# NFC_NXP.net
KiCad netlist of a schematic drawn in Altium Designer
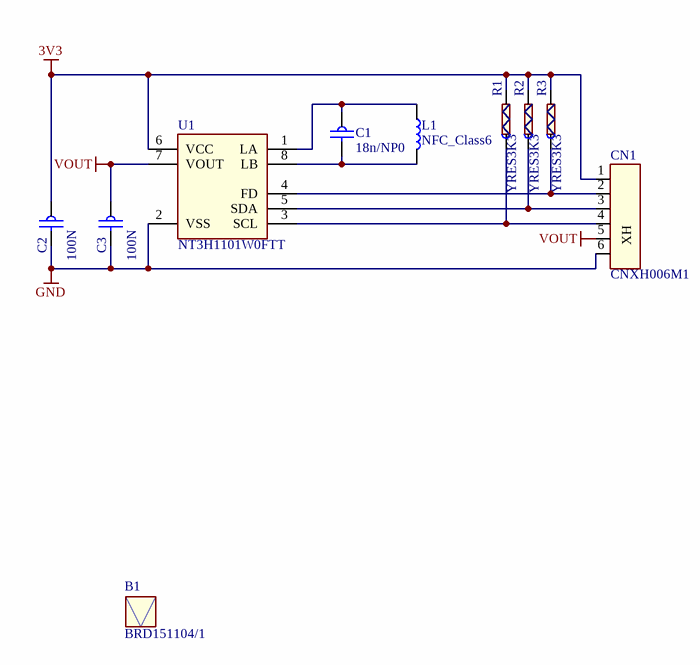
[diagram p0: NFC_NXP.SchDoc]

(export (version "E")
  (design (tool "Eeschema 10.0.6"))
  (components
    (comp (ref "B1")
      (value "~")
      (footprint "MC_BoardNr")
      (description "Bare PCB")
      (libsource (lib "Testing") (part "BD_PCB"))
    )
    (comp (ref "C1")
      (value "18n/NP0")
      (footprint "CA_STD1206_H16")
      (description "18N")
      (libsource (lib "Testing") (part "CA_STD_NonPolar"))
    )
    (comp (ref "C2")
      (value "100N")
      (footprint "CA_STD1206_H16")
      (description "Chip 100N/50V-X7R")
      (libsource (lib "Traficon_TIS_CT") (part "CA_STD_NonPolar"))
    )
    (comp (ref "C3")
      (value "100N")
      (footprint "CA_STD1206_H16")
      (description "Chip 100N/50V-X7R")
      (libsource (lib "Traficon_TIS_CT") (part "CA_STD_NonPolar"))
    )
    (comp (ref "CN1")
      (value "CNXH006M1")
      (footprint "CN_JST-B6B-XH")
      (description "HEADER, VERT, 1x6WAY")
      (libsource (lib "Testing") (part "CN_JST-B6B-XH-A"))
    )
    (comp (ref "L1")
      (value "NFC_Class6")
      (footprint "CL_NFC_Class6")
      (libsource (lib "Testing") (part "CL_STD_PlanarCoil"))
    )
    (comp (ref "R1")
      (value "YRES3K3")
      (footprint "RE_STD1206_H6")
      (description "3K3")
      (libsource (lib "Testing") (part "RE_STD_Resistor"))
    )
    (comp (ref "R2")
      (value "YRES3K3")
      (footprint "RE_STD1206_H6")
      (description "3K3")
      (libsource (lib "Testing") (part "RE_STD_Resistor"))
    )
    (comp (ref "R3")
      (value "YRES3K3")
      (footprint "RE_STD1206_H6")
      (description "3K3")
      (libsource (lib "Testing") (part "RE_STD_Resistor"))
    )
    (comp (ref "U1")
      (value "NT3H1101W0FTT")
      (footprint "SC_TSSOP8_N")
      (libsource (lib "Testing") (part "IC_NT3H1x01"))
    )
  )
  (nets
    (net (code "1") (name "3V3") (class "Default")
      (node (ref "C2") (pin "1") (pinfunction "1_1") (pintype "passive"))
      (node (ref "CN1") (pin "1") (pinfunction "1_1") (pintype "passive"))
      (node (ref "R1") (pin "2") (pinfunction "2_2") (pintype "passive"))
      (node (ref "R2") (pin "2") (pinfunction "2_2") (pintype "passive"))
      (node (ref "R3") (pin "2") (pinfunction "2_2") (pintype "passive"))
      (node (ref "U1") (pin "6") (pinfunction "VCC_6") (pintype "passive"))
    )
    (net (code "2") (name "GND") (class "Default")
      (node (ref "C2") (pin "2") (pinfunction "2_2") (pintype "passive"))
      (node (ref "C3") (pin "2") (pinfunction "2_2") (pintype "passive"))
      (node (ref "CN1") (pin "6") (pinfunction "6_6") (pintype "passive"))
      (node (ref "U1") (pin "2") (pinfunction "VSS_2") (pintype "passive"))
    )
    (net (code "3") (name "Net-(U1-FD)") (class "Default")
      (node (ref "CN1") (pin "2") (pinfunction "2_2") (pintype "passive"))
      (node (ref "R3") (pin "1") (pinfunction "1_1") (pintype "passive"))
      (node (ref "U1") (pin "4") (pinfunction "FD_4") (pintype "passive"))
    )
    (net (code "4") (name "Net-(U1-LA)") (class "Default")
      (node (ref "C1") (pin "1") (pinfunction "1_1") (pintype "passive"))
      (node (ref "L1") (pin "1") (pinfunction "1_1") (pintype "passive"))
      (node (ref "U1") (pin "1") (pinfunction "LA_1") (pintype "passive"))
    )
    (net (code "5") (name "Net-(U1-LB)") (class "Default")
      (node (ref "C1") (pin "2") (pinfunction "2_2") (pintype "passive"))
      (node (ref "L1") (pin "2") (pinfunction "2_2") (pintype "passive"))
      (node (ref "U1") (pin "8") (pinfunction "LB_8") (pintype "passive"))
    )
    (net (code "6") (name "Net-(U1-SCL)") (class "Default")
      (node (ref "CN1") (pin "4") (pinfunction "4_4") (pintype "passive"))
      (node (ref "R1") (pin "1") (pinfunction "1_1") (pintype "passive"))
      (node (ref "U1") (pin "3") (pinfunction "SCL_3") (pintype "passive"))
    )
    (net (code "7") (name "Net-(U1-SDA)") (class "Default")
      (node (ref "CN1") (pin "3") (pinfunction "3_3") (pintype "passive"))
      (node (ref "R2") (pin "1") (pinfunction "1_1") (pintype "passive"))
      (node (ref "U1") (pin "5") (pinfunction "SDA_5") (pintype "passive"))
    )
    (net (code "8") (name "VOUT") (class "Default")
      (node (ref "C3") (pin "1") (pinfunction "1_1") (pintype "passive"))
      (node (ref "CN1") (pin "5") (pinfunction "5_5") (pintype "passive"))
      (node (ref "U1") (pin "7") (pinfunction "VOUT_7") (pintype "passive"))
    )
  )
)
